# Arduino.net
KiCad netlist of a schematic drawn in Altium Designer
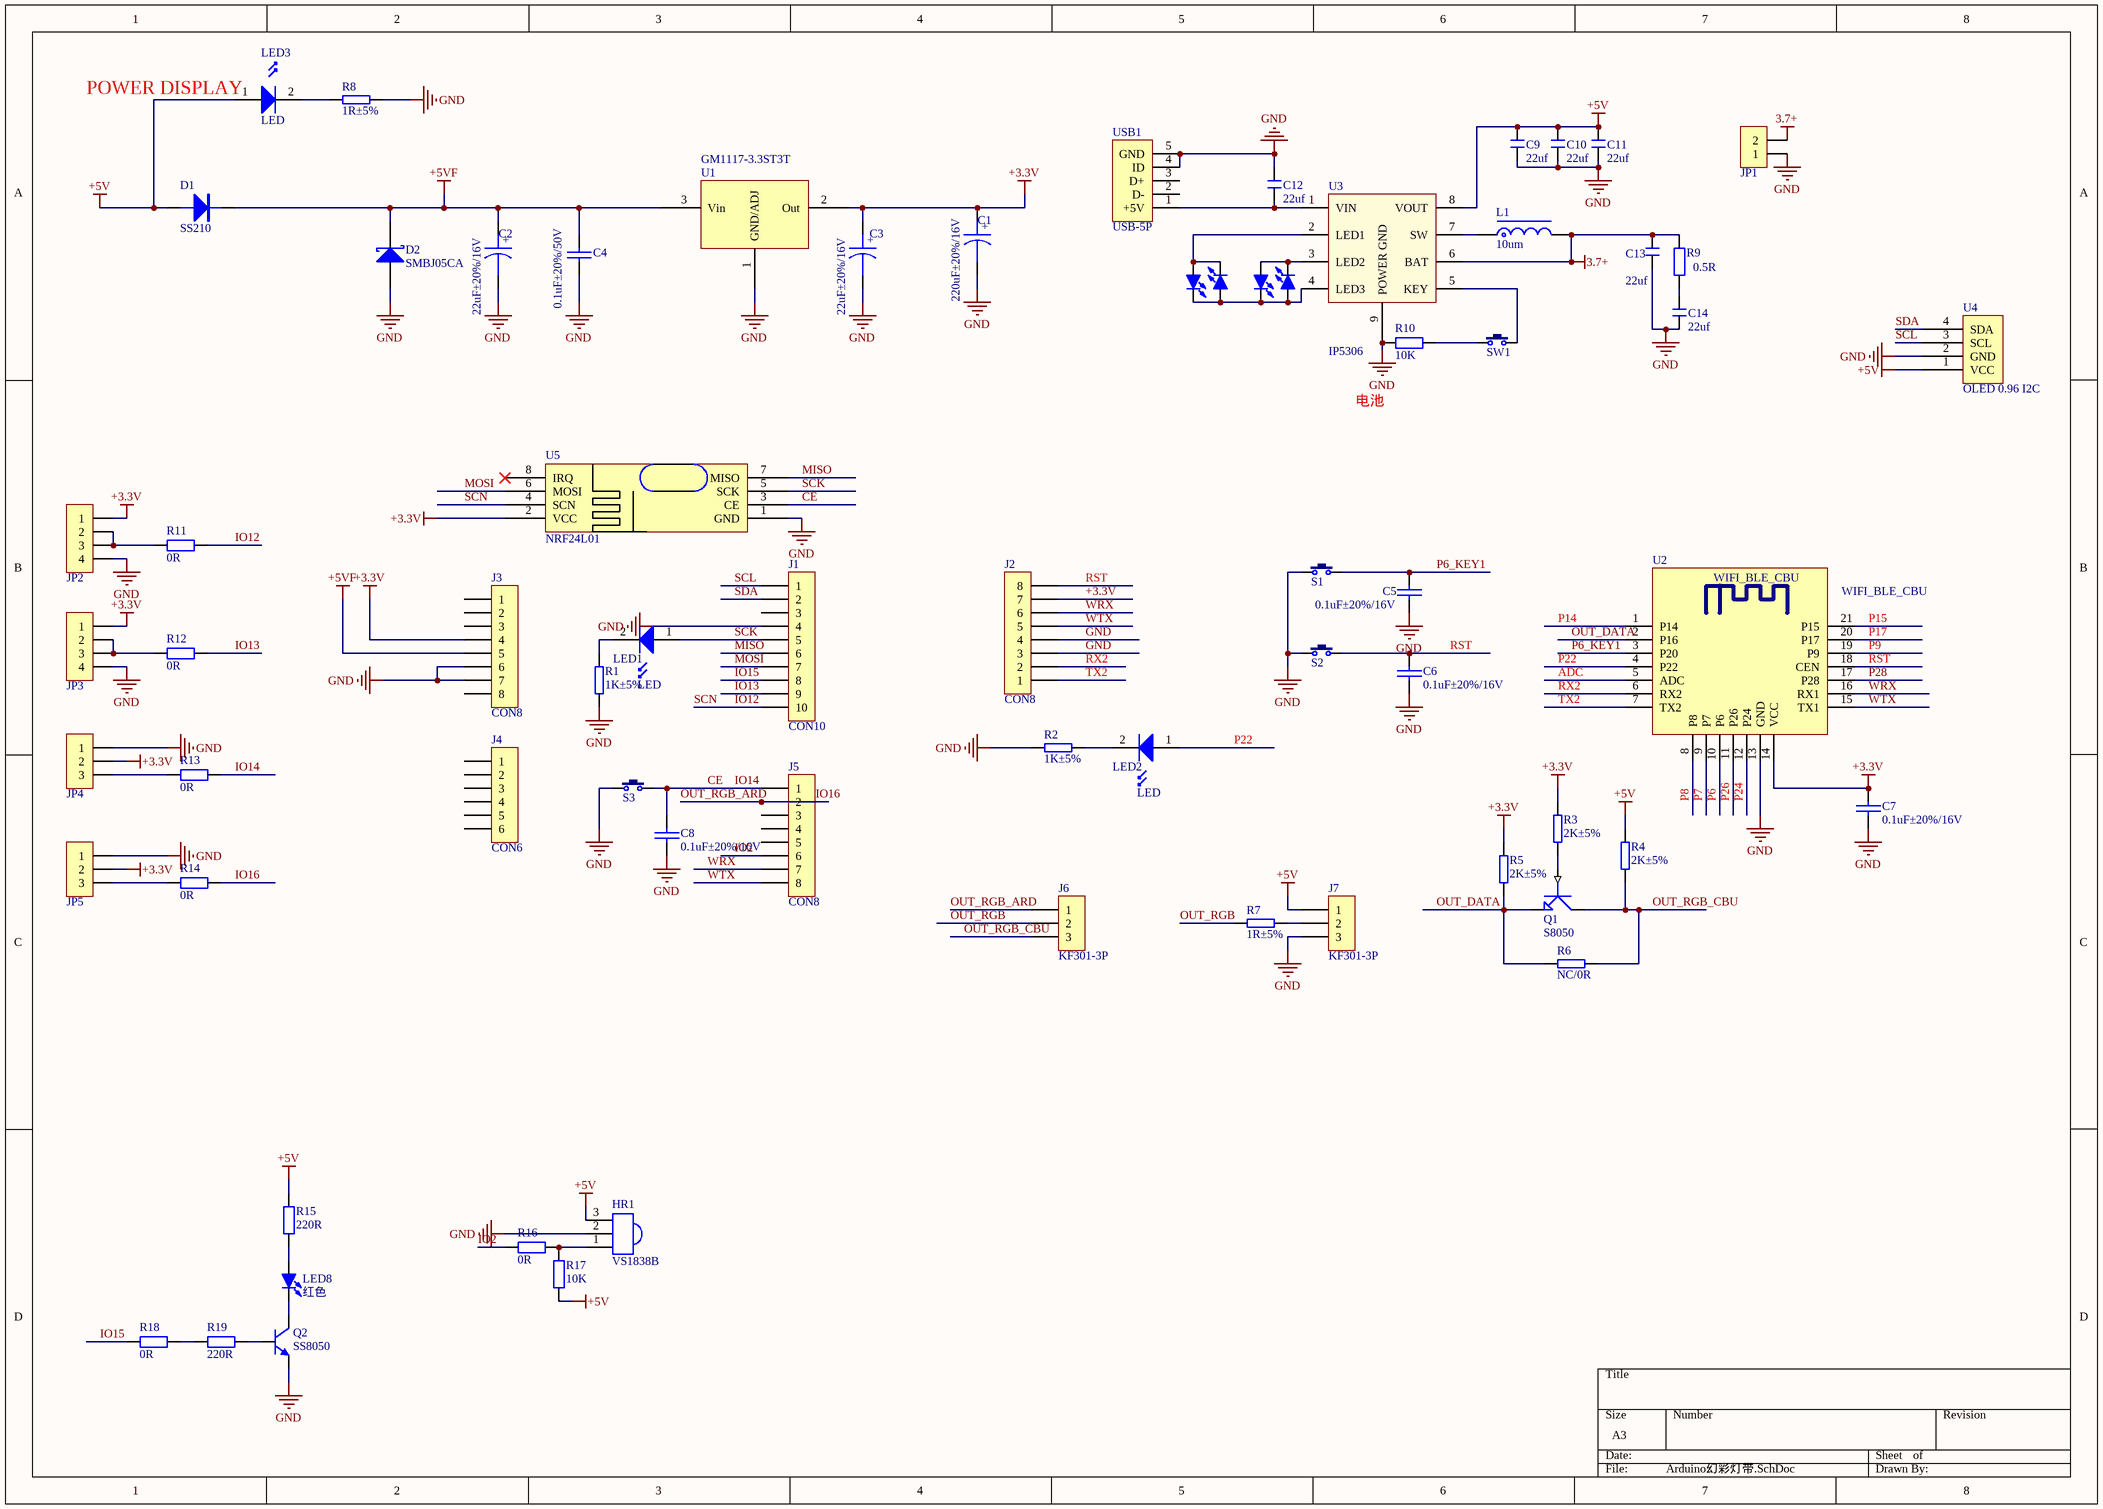
[diagram p0: Arduino幻彩灯带.SchDoc]

(export (version "E")
  (design (tool "Eeschema 10.0.6"))
  (components
    (comp (ref "C1")
      (value "220uF±20%/16V")
      (footprint "CD0.15")
      (description "Capacitor")
      (libsource (lib "*") (part "CAPACITOR POL"))
    )
    (comp (ref "C2")
      (value "22uF±20%/16V")
      (footprint "钽电容B3528")
      (description "Capacitor")
      (libsource (lib "*") (part "CAPACITOR POL"))
    )
    (comp (ref "C3")
      (value "22uF±20%/16V")
      (footprint "钽电容B3528")
      (description "Capacitor")
      (libsource (lib "*") (part "CAPACITOR POL"))
    )
    (comp (ref "C4")
      (value "0.1uF±20%/50V")
      (footprint "C0603")
      (description "Capacitor")
      (libsource (lib "昊华元件库sch") (part "CAP"))
    )
    (comp (ref "C5")
      (value "0.1uF±20%/16V")
      (footprint "C0603")
      (description "Capacitor")
      (libsource (lib "昊华元件库sch") (part "CAP"))
    )
    (comp (ref "C6")
      (value "0.1uF±20%/16V")
      (footprint "C0603")
      (description "Capacitor")
      (libsource (lib "昊华元件库sch") (part "CAP"))
    )
    (comp (ref "C7")
      (value "0.1uF±20%/16V")
      (footprint "C0603")
      (description "Capacitor")
      (libsource (lib "昊华元件库sch") (part "CAP"))
    )
    (comp (ref "C8")
      (value "0.1uF±20%/16V")
      (footprint "C0603")
      (description "Capacitor")
      (libsource (lib "昊华元件库sch") (part "CAP"))
    )
    (comp (ref "C9")
      (value "22uf")
      (footprint "C 0805")
      (description "无极性贴片电容")
      (fields (field (name "版权归属") "源创客"))
      (libsource (lib "电阻-电容-电感") (part "C"))
    )
    (comp (ref "C10")
      (value "22uf")
      (footprint "C 0805")
      (description "无极性贴片电容")
      (fields (field (name "版权归属") "源创客"))
      (libsource (lib "电阻-电容-电感") (part "C"))
    )
    (comp (ref "C11")
      (value "22uf")
      (footprint "C 0805")
      (description "无极性贴片电容")
      (fields (field (name "版权归属") "源创客"))
      (libsource (lib "电阻-电容-电感") (part "C"))
    )
    (comp (ref "C12")
      (value "22uf")
      (footprint "C 0805")
      (description "无极性贴片电容")
      (fields (field (name "版权归属") "源创客"))
      (libsource (lib "电阻-电容-电感") (part "C"))
    )
    (comp (ref "C13")
      (value "22uf")
      (footprint "C 0805")
      (description "无极性贴片电容")
      (fields (field (name "版权归属") "源创客"))
      (libsource (lib "电阻-电容-电感") (part "C"))
    )
    (comp (ref "C14")
      (value "22uf")
      (footprint "C 0805")
      (description "无极性贴片电容")
      (fields (field (name "版权归属") "源创客"))
      (libsource (lib "电阻-电容-电感") (part "C"))
    )
    (comp (ref "D1")
      (value "SS210")
      (footprint "SMA(DO-214AC)")
      (description "Diode")
      (libsource (lib "小马元件库sch") (part "Diode1"))
    )
    (comp (ref "D2")
      (value "SMBJ05CA")
      (footprint "SMB(DO-214AA)")
      (description "Schottky Diode")
      (fields (field (name "MFR") "Toshiba"))
      (libsource (lib "Miscellaneous Devices") (part "D Schottky"))
    )
    (comp (ref "HR1")
      (value "VS1838B")
      (footprint "VS1838B-B")
      (description "红外接收头")
      (fields (field (name "版权归属") "源创客"))
      (libsource (lib "传感元件") (part "VS1838B"))
    )
    (comp (ref "J1")
      (value "CON10")
      (footprint "HDR1X10Z")
      (description "Connector")
      (libsource (lib "小马元件库sch") (part "CON10"))
    )
    (comp (ref "J2")
      (value "CON8")
      (footprint "HDR1X8Z")
      (description "Connector")
      (libsource (lib "小马元件库sch") (part "CON8"))
    )
    (comp (ref "J3")
      (value "CON8")
      (footprint "HDR1X8Z")
      (description "Connector")
      (libsource (lib "") (part "CON8_1"))
    )
    (comp (ref "J4")
      (value "CON6")
      (footprint "HDR1X6Z")
      (description "Connector")
      (libsource (lib "小马元件库sch") (part "CON6"))
    )
    (comp (ref "J5")
      (value "CON8")
      (footprint "HDR1X8Z")
      (description "Connector")
      (libsource (lib "") (part "CON8_1"))
    )
    (comp (ref "J6")
      (value "KF301-3P")
      (footprint "SIP3 - 2.54")
      (description "Connector")
      (libsource (lib "小马元件库sch") (part "CON3"))
    )
    (comp (ref "J7")
      (value "KF301-3P")
      (footprint "SIP3 - 2.54")
      (description "Connector")
      (libsource (lib "小马元件库sch") (part "CON3"))
    )
    (comp (ref "JP1")
      (value "HDR-1X2")
      (footprint "XH2.54-2P_H")
      (description "2P接插件")
      (fields (field (name "版权归属") "源创客"))
      (libsource (lib "接插件") (part "Header 2"))
    )
    (comp (ref "JP2")
      (value "HDR-1X4")
      (footprint "HDR-1X4_M")
      (description "4P接插件")
      (fields (field (name "版权归属") "源创客"))
      (libsource (lib "接插件") (part "Header 4"))
    )
    (comp (ref "JP3")
      (value "HDR-1X4")
      (footprint "HDR-1X4_M")
      (description "4P接插件")
      (fields (field (name "版权归属") "源创客"))
      (libsource (lib "接插件") (part "Header 4"))
    )
    (comp (ref "JP4")
      (value "HDR-1X3")
      (footprint "HDR-1X3_M")
      (description "3P接插件")
      (fields (field (name "版权归属") "源创客"))
      (libsource (lib "接插件") (part "Header 3"))
    )
    (comp (ref "JP5")
      (value "HDR-1X3")
      (footprint "HDR-1X3_M")
      (description "3P接插件")
      (fields (field (name "版权归属") "源创客"))
      (libsource (lib "接插件") (part "Header 3"))
    )
    (comp (ref "L1")
      (value "10um")
      (footprint "CD54")
      (description "贴片功率电感")
      (fields (field (name "版权归属") "源创客"))
      (libsource (lib "电阻-电容-电感") (part "L-CD"))
    )
    (comp (ref "LED1")
      (value "LED")
      (footprint "LED0805_1")
      (fields (field (name "PUBLISHER") "*"))
      (libsource (lib "小马元件库sch") (part "LED"))
    )
    (comp (ref "LED2")
      (value "LED")
      (footprint "LED0805_1")
      (fields (field (name "PUBLISHER") "*"))
      (libsource (lib "小马元件库sch") (part "LED"))
    )
    (comp (ref "LED3")
      (value "LED")
      (footprint "LED0805_1")
      (fields (field (name "PUBLISHER") "*"))
      (libsource (lib "小马元件库sch") (part "LED"))
    )
    (comp (ref "LED4")
      (value "蓝色")
      (footprint "LED 0805B")
      (description "贴片LED")
      (fields (field (name "版权归属") "源创客"))
      (libsource (lib "LED") (part "LED-SMD"))
    )
    (comp (ref "LED5")
      (value "蓝色")
      (footprint "LED 0805B")
      (description "贴片LED")
      (fields (field (name "版权归属") "源创客"))
      (libsource (lib "LED") (part "LED-SMD"))
    )
    (comp (ref "LED6")
      (value "蓝色")
      (footprint "LED 0805B")
      (description "贴片LED")
      (fields (field (name "版权归属") "源创客"))
      (libsource (lib "LED") (part "LED-SMD"))
    )
    (comp (ref "LED7")
      (value "蓝色")
      (footprint "LED 0805B")
      (description "贴片LED")
      (fields (field (name "版权归属") "源创客"))
      (libsource (lib "LED") (part "LED-SMD"))
    )
    (comp (ref "LED8")
      (value "红色")
      (footprint "LED 5MM-B")
      (description "5mm插件LED")
      (fields (field (name "版权归属") "源创客"))
      (libsource (lib "LED") (part "LED-5MM"))
    )
    (comp (ref "Q1")
      (value "S8050")
      (footprint "SOT-23-NPN")
      (description "NPN Transistor")
      (libsource (lib "小马元件库sch") (part "NPN"))
    )
    (comp (ref "Q2")
      (value "SS8050")
      (footprint "SOT23-3N")
      (description "高频放大-NPN型")
      (fields (field (name "版权归属") "源创客"))
      (libsource (lib "三极管") (part "8050-SMD"))
    )
    (comp (ref "R1") (value "1K±5%") (footprint "R0603") (libsource (lib "昊华元件库sch") (part "RES5")))
    (comp (ref "R2") (value "1K±5%") (footprint "R0603") (libsource (lib "昊华元件库sch") (part "RES5")))
    (comp (ref "R3") (value "2K±5%") (footprint "R0603") (libsource (lib "昊华元件库sch") (part "RES5")))
    (comp (ref "R4") (value "2K±5%") (footprint "R0603") (libsource (lib "昊华元件库sch") (part "RES5")))
    (comp (ref "R5") (value "2K±5%") (footprint "R0603") (libsource (lib "昊华元件库sch") (part "RES5")))
    (comp (ref "R6") (value "NC/0R") (footprint "R0603") (libsource (lib "昊华元件库sch") (part "RES5")))
    (comp (ref "R7") (value "1R±5%") (footprint "R0603") (libsource (lib "昊华元件库sch") (part "RES5")))
    (comp (ref "R8") (value "1R±5%") (footprint "R0603") (libsource (lib "昊华元件库sch") (part "RES5")))
    (comp (ref "R9")
      (value "0.5R")
      (footprint "R 0805")
      (description "贴片电阻")
      (fields (field (name "版权归属") "源创客"))
      (libsource (lib "电阻-电容-电感") (part "R"))
    )
    (comp (ref "R10")
      (value "10K")
      (footprint "R 0805")
      (description "贴片电阻")
      (fields (field (name "版权归属") "源创客"))
      (libsource (lib "电阻-电容-电感") (part "R"))
    )
    (comp (ref "R11")
      (value "0R")
      (footprint "R 0603")
      (description "贴片电阻")
      (fields (field (name "版权归属") "源创客"))
      (libsource (lib "电阻-电容-电感") (part "R"))
    )
    (comp (ref "R12")
      (value "0R")
      (footprint "R 0603")
      (description "贴片电阻")
      (fields (field (name "版权归属") "源创客"))
      (libsource (lib "电阻-电容-电感") (part "R"))
    )
    (comp (ref "R13")
      (value "0R")
      (footprint "R 0603")
      (description "贴片电阻")
      (fields (field (name "版权归属") "源创客"))
      (libsource (lib "电阻-电容-电感") (part "R"))
    )
    (comp (ref "R14")
      (value "0R")
      (footprint "R 0603")
      (description "贴片电阻")
      (fields (field (name "版权归属") "源创客"))
      (libsource (lib "电阻-电容-电感") (part "R"))
    )
    (comp (ref "R15")
      (value "220R")
      (footprint "R 0603")
      (description "贴片电阻")
      (fields (field (name "版权归属") "源创客"))
      (libsource (lib "电阻-电容-电感") (part "R"))
    )
    (comp (ref "R16")
      (value "0R")
      (footprint "R 0603")
      (description "贴片电阻")
      (fields (field (name "版权归属") "源创客"))
      (libsource (lib "电阻-电容-电感") (part "R"))
    )
    (comp (ref "R17")
      (value "10K")
      (footprint "R 0603")
      (description "贴片电阻")
      (fields (field (name "版权归属") "源创客"))
      (libsource (lib "电阻-电容-电感") (part "R"))
    )
    (comp (ref "R18")
      (value "0R")
      (footprint "R 0603")
      (description "贴片电阻")
      (fields (field (name "版权归属") "源创客"))
      (libsource (lib "电阻-电容-电感") (part "R"))
    )
    (comp (ref "R19")
      (value "220R")
      (footprint "R 0603")
      (description "贴片电阻")
      (fields (field (name "版权归属") "源创客"))
      (libsource (lib "电阻-电容-电感") (part "R"))
    )
    (comp (ref "S1")
      (value "3x6x5")
      (footprint "TSW SMD-3*6*2.5")
      (description "3x6轻触开关")
      (fields (field (name "版权归属") "源创客"))
      (libsource (lib "按键-开关") (part "TSW 3x6"))
    )
    (comp (ref "S2")
      (value "3x6x5")
      (footprint "TSW SMD-3*6*2.5")
      (description "3x6轻触开关")
      (fields (field (name "版权归属") "源创客"))
      (libsource (lib "按键-开关") (part "TSW 3x6"))
    )
    (comp (ref "S3")
      (value "3x6x5")
      (footprint "TSW SMD-3*6*2.5")
      (description "3x6轻触开关")
      (fields (field (name "版权归属") "源创客"))
      (libsource (lib "按键-开关") (part "TSW 3x6"))
    )
    (comp (ref "SW1")
      (value "3x6x5")
      (footprint "TSW SMD-3*6*2.5")
      (description "3x6轻触开关")
      (fields (field (name "版权归属") "源创客"))
      (libsource (lib "按键-开关") (part "TSW 3x6"))
    )
    (comp (ref "U1") (value "GM1117-3.3ST3T") (footprint "SOT-223") (libsource (lib "mylib") (part "GM1117")))
    (comp (ref "U2")
      (value "WIFI_BLE_CBU")
      (footprint "WIFI_BLE_CBU")
      (description "Module")
      (libsource (lib "TYModeSchlib V03") (part "WIFI_BLE_CBU"))
    )
    (comp (ref "U3")
      (value "IP5306")
      (footprint "5306")
      (description "锂电池充放电管理芯片")
      (libsource (lib "电源管理类芯片") (part "IP5306"))
    )
    (comp (ref "U4")
      (value "OLED 0.96 I2C")
      (footprint "OLED 0.96 I2C")
      (libsource (lib "显示器件") (part "OLED 0.96 I2C"))
    )
    (comp (ref "U5")
      (value "NRF24L01")
      (footprint "NRF24L01")
      (description "2.4G无线模块")
      (libsource (lib "模块") (part "NRF24L01"))
    )
    (comp (ref "USB1")
      (value "USB-5P")
      (footprint "USB-MICRO_B")
      (description "微型USB母座")
      (fields (field (name "版权归属") "源创客"))
      (libsource (lib "接口类") (part "USB-5P"))
    )
  )
  (nets
    (net (code "1") (name "+3.3V") (class "Default")
      (node (ref "C1") (pin "1") (pinfunction "1_1") (pintype "passive"))
      (node (ref "C3") (pin "1") (pinfunction "1_1") (pintype "passive"))
      (node (ref "C7") (pin "2") (pinfunction "2_2") (pintype "passive"))
      (node (ref "J2") (pin "7") (pinfunction "7_7") (pintype "passive"))
      (node (ref "J3") (pin "4") (pinfunction "4_4") (pintype "passive"))
      (node (ref "JP2") (pin "1") (pinfunction "1_1") (pintype "passive"))
      (node (ref "JP3") (pin "1") (pinfunction "1_1") (pintype "passive"))
      (node (ref "JP4") (pin "2") (pinfunction "2_2") (pintype "passive"))
      (node (ref "JP5") (pin "2") (pinfunction "2_2") (pintype "passive"))
      (node (ref "R3") (pin "1") (pinfunction "1_1") (pintype "passive"))
      (node (ref "R5") (pin "1") (pinfunction "1_1") (pintype "passive"))
      (node (ref "U1") (pin "2") (pinfunction "Out_2") (pintype "passive"))
      (node (ref "U2") (pin "14") (pinfunction "VCC_14") (pintype "passive"))
      (node (ref "U5") (pin "2") (pinfunction "VCC_2") (pintype "power_in"))
    )
    (net (code "2") (name "+5V") (class "Default")
      (node (ref "C10") (pin "2") (pinfunction "2_2") (pintype "passive"))
      (node (ref "C11") (pin "2") (pinfunction "2_2") (pintype "passive"))
      (node (ref "C9") (pin "2") (pinfunction "2_2") (pintype "passive"))
      (node (ref "D1") (pin "1") (pinfunction "1_1") (pintype "passive"))
      (node (ref "HR1") (pin "3") (pinfunction "E_3") (pintype "passive"))
      (node (ref "J7") (pin "1") (pinfunction "1_1") (pintype "passive"))
      (node (ref "LED3") (pin "1") (pinfunction "1_1") (pintype "passive"))
      (node (ref "R15") (pin "2") (pinfunction "2_2") (pintype "passive"))
      (node (ref "R17") (pin "1") (pinfunction "1_1") (pintype "passive"))
      (node (ref "R4") (pin "1") (pinfunction "1_1") (pintype "passive"))
      (node (ref "U3") (pin "8") (pinfunction "VOUT_8") (pintype "passive"))
      (node (ref "U4") (pin "1") (pinfunction "VCC_1") (pintype "power_in"))
    )
    (net (code "3") (name "+5VF") (class "Default")
      (node (ref "C2") (pin "1") (pinfunction "1_1") (pintype "passive"))
      (node (ref "C4") (pin "1") (pinfunction "1_1") (pintype "passive"))
      (node (ref "D1") (pin "2") (pinfunction "2_2") (pintype "passive"))
      (node (ref "D2") (pin "2") (pinfunction "K_2") (pintype "passive"))
      (node (ref "J3") (pin "5") (pinfunction "5_5") (pintype "passive"))
      (node (ref "U1") (pin "3") (pinfunction "Vin_3") (pintype "passive"))
    )
    (net (code "4") (name "/ADC") (class "Default")
      (node (ref "U2") (pin "5") (pinfunction "ADC_5") (pintype "passive"))
    )
    (net (code "5") (name "/CE") (class "Default")
      (node (ref "C8") (pin "2") (pinfunction "2_2") (pintype "passive"))
      (node (ref "J5") (pin "1") (pinfunction "1_1") (pintype "passive"))
      (node (ref "R13") (pin "2") (pinfunction "2_2") (pintype "passive"))
      (node (ref "S3") (pin "2") (pinfunction "2_2") (pintype "passive"))
      (node (ref "U5") (pin "3") (pinfunction "CE_3") (pintype "power_in"))
    )
    (net (code "6") (name "/IO2") (class "Default")
      (node (ref "J5") (pin "6") (pinfunction "6_6") (pintype "passive"))
      (node (ref "R16") (pin "1") (pinfunction "1_1") (pintype "passive"))
    )
    (net (code "7") (name "/IO12") (class "Default")
      (node (ref "J1") (pin "10") (pinfunction "10_10") (pintype "passive"))
      (node (ref "R11") (pin "2") (pinfunction "2_2") (pintype "passive"))
      (node (ref "U5") (pin "4") (pinfunction "SCN_4") (pintype "power_in"))
    )
    (net (code "8") (name "/IO13") (class "Default")
      (node (ref "J1") (pin "9") (pinfunction "9_9") (pintype "passive"))
      (node (ref "R12") (pin "2") (pinfunction "2_2") (pintype "passive"))
    )
    (net (code "9") (name "/IO15") (class "Default")
      (node (ref "J1") (pin "8") (pinfunction "8_8") (pintype "passive"))
      (node (ref "R18") (pin "1") (pinfunction "1_1") (pintype "passive"))
    )
    (net (code "10") (name "/IO16") (class "Default")
      (node (ref "J5") (pin "2") (pinfunction "2_2") (pintype "passive"))
      (node (ref "J6") (pin "1") (pinfunction "1_1") (pintype "passive"))
      (node (ref "R14") (pin "2") (pinfunction "2_2") (pintype "passive"))
    )
    (net (code "11") (name "/MISO") (class "Default")
      (node (ref "J1") (pin "6") (pinfunction "6_6") (pintype "passive"))
      (node (ref "U5") (pin "7") (pinfunction "MISO_7") (pintype "power_in"))
    )
    (net (code "12") (name "/MOSI") (class "Default")
      (node (ref "J1") (pin "7") (pinfunction "7_7") (pintype "passive"))
      (node (ref "U5") (pin "6") (pinfunction "MOSI_6") (pintype "power_in"))
    )
    (net (code "13") (name "/OUT_DATA") (class "Default")
      (node (ref "Q1") (pin "1") (pinfunction "E_1") (pintype "passive"))
      (node (ref "R5") (pin "2") (pinfunction "2_2") (pintype "passive"))
      (node (ref "R6") (pin "1") (pinfunction "1_1") (pintype "passive"))
      (node (ref "U2") (pin "2") (pinfunction "P16_2") (pintype "passive"))
    )
    (net (code "14") (name "/OUT_RGB") (class "Default")
      (node (ref "J6") (pin "2") (pinfunction "2_2") (pintype "passive"))
      (node (ref "R7") (pin "1") (pinfunction "1_1") (pintype "passive"))
    )
    (net (code "15") (name "/OUT_RGB_CBU") (class "Default")
      (node (ref "J6") (pin "3") (pinfunction "3_3") (pintype "passive"))
      (node (ref "Q1") (pin "3") (pinfunction "C_3") (pintype "passive"))
      (node (ref "R4") (pin "2") (pinfunction "2_2") (pintype "passive"))
      (node (ref "R6") (pin "2") (pinfunction "2_2") (pintype "passive"))
    )
    (net (code "16") (name "/P6") (class "Default")
      (node (ref "U2") (pin "10") (pinfunction "P6_10") (pintype "passive"))
    )
    (net (code "17") (name "/P6_KEY1") (class "Default")
      (node (ref "C5") (pin "2") (pinfunction "2_2") (pintype "passive"))
      (node (ref "S1") (pin "2") (pinfunction "2_2") (pintype "passive"))
      (node (ref "U2") (pin "3") (pinfunction "P20_3") (pintype "passive"))
    )
    (net (code "18") (name "/P7") (class "Default")
      (node (ref "U2") (pin "9") (pinfunction "P7_9") (pintype "passive"))
    )
    (net (code "19") (name "/P8") (class "Default")
      (node (ref "U2") (pin "8") (pinfunction "P8_8") (pintype "passive"))
    )
    (net (code "20") (name "/P9") (class "Default")
      (node (ref "U2") (pin "19") (pinfunction "P9_19") (pintype "passive"))
    )
    (net (code "21") (name "/P14") (class "Default")
      (node (ref "U2") (pin "1") (pinfunction "P14_1") (pintype "passive"))
    )
    (net (code "22") (name "/P15") (class "Default")
      (node (ref "U2") (pin "21") (pinfunction "P15_21") (pintype "passive"))
    )
    (net (code "23") (name "/P17") (class "Default")
      (node (ref "U2") (pin "20") (pinfunction "P17_20") (pintype "passive"))
    )
    (net (code "24") (name "/P22") (class "Default")
      (node (ref "LED2") (pin "1") (pinfunction "1_1") (pintype "passive"))
      (node (ref "U2") (pin "4") (pinfunction "P22_4") (pintype "passive"))
    )
    (net (code "25") (name "/P24") (class "Default")
      (node (ref "U2") (pin "12") (pinfunction "P24_12") (pintype "passive"))
    )
    (net (code "26") (name "/P26") (class "Default")
      (node (ref "U2") (pin "11") (pinfunction "P26_11") (pintype "passive"))
    )
    (net (code "27") (name "/P28") (class "Default")
      (node (ref "U2") (pin "17") (pinfunction "P28_17") (pintype "passive"))
    )
    (net (code "28") (name "/RST") (class "Default")
      (node (ref "C6") (pin "1") (pinfunction "1_1") (pintype "passive"))
      (node (ref "J2") (pin "8") (pinfunction "8_8") (pintype "passive"))
      (node (ref "S2") (pin "2") (pinfunction "2_2") (pintype "passive"))
      (node (ref "U2") (pin "18") (pinfunction "CEN_18") (pintype "passive"))
    )
    (net (code "29") (name "/RX2") (class "Default")
      (node (ref "J2") (pin "2") (pinfunction "2_2") (pintype "passive"))
      (node (ref "U2") (pin "6") (pinfunction "RX2_6") (pintype "passive"))
    )
    (net (code "30") (name "/SCK") (class "Default")
      (node (ref "J1") (pin "5") (pinfunction "5_5") (pintype "passive"))
      (node (ref "LED1") (pin "1") (pinfunction "1_1") (pintype "passive"))
      (node (ref "U5") (pin "5") (pinfunction "SCK_5") (pintype "power_in"))
    )
    (net (code "31") (name "/SCL") (class "Default")
      (node (ref "J1") (pin "1") (pinfunction "1_1") (pintype "passive"))
      (node (ref "U4") (pin "3") (pinfunction "SCL_3") (pintype "power_in"))
    )
    (net (code "32") (name "/SDA") (class "Default")
      (node (ref "J1") (pin "2") (pinfunction "2_2") (pintype "passive"))
      (node (ref "U4") (pin "4") (pinfunction "SDA_4") (pintype "power_in"))
    )
    (net (code "33") (name "/TX2") (class "Default")
      (node (ref "J2") (pin "1") (pinfunction "1_1") (pintype "passive"))
      (node (ref "U2") (pin "7") (pinfunction "TX2_7") (pintype "passive"))
    )
    (net (code "34") (name "/WRX") (class "Default")
      (node (ref "J2") (pin "6") (pinfunction "6_6") (pintype "passive"))
      (node (ref "J5") (pin "7") (pinfunction "7_7") (pintype "passive"))
      (node (ref "U2") (pin "16") (pinfunction "RX1_16") (pintype "passive"))
    )
    (net (code "35") (name "/WTX") (class "Default")
      (node (ref "J2") (pin "5") (pinfunction "5_5") (pintype "passive"))
      (node (ref "J5") (pin "8") (pinfunction "8_8") (pintype "passive"))
      (node (ref "U2") (pin "15") (pinfunction "TX1_15") (pintype "passive"))
    )
    (net (code "36") (name "3.7+") (class "Default")
      (node (ref "C13") (pin "2") (pinfunction "2_2") (pintype "passive"))
      (node (ref "JP1") (pin "2") (pinfunction "2_2") (pintype "passive"))
      (node (ref "L1") (pin "2") (pinfunction "2_2") (pintype "passive"))
      (node (ref "R9") (pin "2") (pinfunction "2_2") (pintype "passive"))
      (node (ref "U3") (pin "6") (pinfunction "BAT_6") (pintype "passive"))
    )
    (net (code "37") (name "GND") (class "Default")
      (node (ref "C1") (pin "2") (pinfunction "2_2") (pintype "passive"))
      (node (ref "C10") (pin "1") (pinfunction "1_1") (pintype "passive"))
      (node (ref "C11") (pin "1") (pinfunction "1_1") (pintype "passive"))
      (node (ref "C12") (pin "2") (pinfunction "2_2") (pintype "passive"))
      (node (ref "C13") (pin "1") (pinfunction "1_1") (pintype "passive"))
      (node (ref "C14") (pin "1") (pinfunction "1_1") (pintype "passive"))
      (node (ref "C2") (pin "2") (pinfunction "2_2") (pintype "passive"))
      (node (ref "C3") (pin "2") (pinfunction "2_2") (pintype "passive"))
      (node (ref "C4") (pin "2") (pinfunction "2_2") (pintype "passive"))
      (node (ref "C5") (pin "1") (pinfunction "1_1") (pintype "passive"))
      (node (ref "C6") (pin "2") (pinfunction "2_2") (pintype "passive"))
      (node (ref "C7") (pin "1") (pinfunction "1_1") (pintype "passive"))
      (node (ref "C8") (pin "1") (pinfunction "1_1") (pintype "passive"))
      (node (ref "C9") (pin "1") (pinfunction "1_1") (pintype "passive"))
      (node (ref "D2") (pin "1") (pinfunction "A_1") (pintype "passive"))
      (node (ref "HR1") (pin "2") (pinfunction "K_2") (pintype "passive"))
      (node (ref "J1") (pin "4") (pinfunction "4_4") (pintype "passive"))
      (node (ref "J2") (pin "3") (pinfunction "3_3") (pintype "passive"))
      (node (ref "J2") (pin "4") (pinfunction "4_4") (pintype "passive"))
      (node (ref "J3") (pin "6") (pinfunction "6_6") (pintype "passive"))
      (node (ref "J3") (pin "7") (pinfunction "7_7") (pintype "passive"))
      (node (ref "J7") (pin "3") (pinfunction "3_3") (pintype "passive"))
      (node (ref "JP1") (pin "1") (pinfunction "1_1") (pintype "passive"))
      (node (ref "JP2") (pin "4") (pinfunction "4_4") (pintype "passive"))
      (node (ref "JP3") (pin "4") (pinfunction "4_4") (pintype "passive"))
      (node (ref "JP4") (pin "1") (pinfunction "1_1") (pintype "passive"))
      (node (ref "JP5") (pin "1") (pinfunction "1_1") (pintype "passive"))
      (node (ref "Q2") (pin "2") (pinfunction "E_2") (pintype "passive"))
      (node (ref "R1") (pin "1") (pinfunction "1_1") (pintype "passive"))
      (node (ref "R10") (pin "1") (pinfunction "1_1") (pintype "passive"))
      (node (ref "R2") (pin "2") (pinfunction "2_2") (pintype "passive"))
      (node (ref "R8") (pin "2") (pinfunction "2_2") (pintype "passive"))
      (node (ref "S1") (pin "1") (pinfunction "1_1") (pintype "passive"))
      (node (ref "S2") (pin "1") (pinfunction "1_1") (pintype "passive"))
      (node (ref "S3") (pin "1") (pinfunction "1_1") (pintype "passive"))
      (node (ref "U1") (pin "1") (pinfunction "GND/ADJ_1") (pintype "passive"))
      (node (ref "U2") (pin "13") (pinfunction "GND_13") (pintype "passive"))
      (node (ref "U3") (pin "9") (pinfunction "POWER_GND_9") (pintype "power_in"))
      (node (ref "U4") (pin "2") (pinfunction "GND_2") (pintype "power_in"))
      (node (ref "U5") (pin "1") (pinfunction "GND_1") (pintype "power_in"))
      (node (ref "USB1") (pin "4") (pinfunction "ID_4") (pintype "passive"))
      (node (ref "USB1") (pin "5") (pinfunction "GND_5") (pintype "passive"))
    )
    (net (code "38") (name "Net-(C14-Pad2)") (class "Default")
      (node (ref "C14") (pin "2") (pinfunction "2_2") (pintype "passive"))
      (node (ref "R9") (pin "1") (pinfunction "1_1") (pintype "passive"))
    )
    (net (code "39") (name "Net-(HR1-A)") (class "Default")
      (node (ref "HR1") (pin "1") (pinfunction "A_1") (pintype "passive"))
      (node (ref "R16") (pin "2") (pinfunction "2_2") (pintype "passive"))
      (node (ref "R17") (pin "2") (pinfunction "2_2") (pintype "passive"))
    )
    (net (code "40") (name "Net-(J7-Pad2)") (class "Default")
      (node (ref "J7") (pin "2") (pinfunction "2_2") (pintype "passive"))
      (node (ref "R7") (pin "2") (pinfunction "2_2") (pintype "passive"))
    )
    (net (code "41") (name "Net-(JP2-Pad2)") (class "Default")
      (node (ref "JP2") (pin "2") (pinfunction "2_2") (pintype "passive"))
      (node (ref "JP2") (pin "3") (pinfunction "3_3") (pintype "passive"))
      (node (ref "R11") (pin "1") (pinfunction "1_1") (pintype "passive"))
    )
    (net (code "42") (name "Net-(JP3-Pad2)") (class "Default")
      (node (ref "JP3") (pin "2") (pinfunction "2_2") (pintype "passive"))
      (node (ref "JP3") (pin "3") (pinfunction "3_3") (pintype "passive"))
      (node (ref "R12") (pin "1") (pinfunction "1_1") (pintype "passive"))
    )
    (net (code "43") (name "Net-(JP4-Pad3)") (class "Default")
      (node (ref "JP4") (pin "3") (pinfunction "3_3") (pintype "passive"))
      (node (ref "R13") (pin "1") (pinfunction "1_1") (pintype "passive"))
    )
    (net (code "44") (name "Net-(JP5-Pad3)") (class "Default")
      (node (ref "JP5") (pin "3") (pinfunction "3_3") (pintype "passive"))
      (node (ref "R14") (pin "1") (pinfunction "1_1") (pintype "passive"))
    )
    (net (code "45") (name "Net-(LED1-Pad2)") (class "Default")
      (node (ref "LED1") (pin "2") (pinfunction "2_2") (pintype "passive"))
      (node (ref "R1") (pin "2") (pinfunction "2_2") (pintype "passive"))
    )
    (net (code "46") (name "Net-(LED2-Pad2)") (class "Default")
      (node (ref "LED2") (pin "2") (pinfunction "2_2") (pintype "passive"))
      (node (ref "R2") (pin "1") (pinfunction "1_1") (pintype "passive"))
    )
    (net (code "47") (name "Net-(LED3-Pad2)") (class "Default")
      (node (ref "LED3") (pin "2") (pinfunction "2_2") (pintype "passive"))
      (node (ref "R8") (pin "1") (pinfunction "1_1") (pintype "passive"))
    )
    (net (code "48") (name "Net-(LED4-A)") (class "Default")
      (node (ref "LED4") (pin "1") (pinfunction "A_1") (pintype "passive"))
      (node (ref "LED5") (pin "1") (pinfunction "A_1") (pintype "passive"))
      (node (ref "LED6") (pin "2") (pinfunction "K_2") (pintype "passive"))
      (node (ref "LED7") (pin "2") (pinfunction "K_2") (pintype "passive"))
      (node (ref "U3") (pin "4") (pinfunction "LED3_4") (pintype "passive"))
    )
    (net (code "49") (name "Net-(LED4-K)") (class "Default")
      (node (ref "LED4") (pin "2") (pinfunction "K_2") (pintype "passive"))
      (node (ref "LED6") (pin "1") (pinfunction "A_1") (pintype "passive"))
      (node (ref "U3") (pin "2") (pinfunction "LED1_2") (pintype "passive"))
    )
    (net (code "50") (name "Net-(LED5-K)") (class "Default")
      (node (ref "LED5") (pin "2") (pinfunction "K_2") (pintype "passive"))
      (node (ref "LED7") (pin "1") (pinfunction "A_1") (pintype "passive"))
      (node (ref "U3") (pin "3") (pinfunction "LED2_3") (pintype "passive"))
    )
    (net (code "51") (name "Net-(LED8-A)") (class "Default")
      (node (ref "LED8") (pin "1") (pinfunction "A_1") (pintype "passive"))
      (node (ref "R15") (pin "1") (pinfunction "1_1") (pintype "passive"))
    )
    (net (code "52") (name "Net-(LED8-K)") (class "Default")
      (node (ref "LED8") (pin "2") (pinfunction "K_2") (pintype "passive"))
      (node (ref "Q2") (pin "3") (pinfunction "C_3") (pintype "passive"))
    )
    (net (code "53") (name "Net-(Q1-B)") (class "Default")
      (node (ref "Q1") (pin "2") (pinfunction "B_2") (pintype "input"))
      (node (ref "R3") (pin "2") (pinfunction "2_2") (pintype "passive"))
    )
    (net (code "54") (name "Net-(Q2-B)") (class "Default")
      (node (ref "Q2") (pin "1") (pinfunction "B_1") (pintype "passive"))
      (node (ref "R19") (pin "2") (pinfunction "2_2") (pintype "passive"))
    )
    (net (code "55") (name "Net-(R10-Pad2)") (class "Default")
      (node (ref "R10") (pin "2") (pinfunction "2_2") (pintype "passive"))
      (node (ref "SW1") (pin "1") (pinfunction "1_1") (pintype "passive"))
    )
    (net (code "56") (name "Net-(R18-Pad2)") (class "Default")
      (node (ref "R18") (pin "2") (pinfunction "2_2") (pintype "passive"))
      (node (ref "R19") (pin "1") (pinfunction "1_1") (pintype "passive"))
    )
    (net (code "57") (name "Net-(U3-KEY)") (class "Default")
      (node (ref "SW1") (pin "2") (pinfunction "2_2") (pintype "passive"))
      (node (ref "U3") (pin "5") (pinfunction "KEY_5") (pintype "passive"))
    )
    (net (code "58") (name "Net-(U3-SW)") (class "Default")
      (node (ref "L1") (pin "1") (pinfunction "1_1") (pintype "passive"))
      (node (ref "U3") (pin "7") (pinfunction "SW_7") (pintype "passive"))
    )
    (net (code "59") (name "Net-(U3-VIN)") (class "Default")
      (node (ref "C12") (pin "1") (pinfunction "1_1") (pintype "passive"))
      (node (ref "U3") (pin "1") (pinfunction "VIN_1") (pintype "passive"))
      (node (ref "USB1") (pin "1") (pinfunction "+5V_1") (pintype "passive"))
    )
    (net (code "60") (name "unconnected-(J1-Pad3)") (class "Default")
      (node (ref "J1") (pin "3") (pinfunction "3_3") (pintype "passive"))
    )
    (net (code "61") (name "unconnected-(J3-Pad1)") (class "Default")
      (node (ref "J3") (pin "1") (pinfunction "1_1") (pintype "passive"))
    )
    (net (code "62") (name "unconnected-(J3-Pad2)") (class "Default")
      (node (ref "J3") (pin "2") (pinfunction "2_2") (pintype "passive"))
    )
    (net (code "63") (name "unconnected-(J3-Pad3)") (class "Default")
      (node (ref "J3") (pin "3") (pinfunction "3_3") (pintype "passive"))
    )
    (net (code "64") (name "unconnected-(J3-Pad8)") (class "Default")
      (node (ref "J3") (pin "8") (pinfunction "8_8") (pintype "passive"))
    )
    (net (code "65") (name "unconnected-(J4-Pad1)") (class "Default")
      (node (ref "J4") (pin "1") (pinfunction "1_1") (pintype "passive"))
    )
    (net (code "66") (name "unconnected-(J4-Pad2)") (class "Default")
      (node (ref "J4") (pin "2") (pinfunction "2_2") (pintype "passive"))
    )
    (net (code "67") (name "unconnected-(J4-Pad3)") (class "Default")
      (node (ref "J4") (pin "3") (pinfunction "3_3") (pintype "passive"))
    )
    (net (code "68") (name "unconnected-(J4-Pad4)") (class "Default")
      (node (ref "J4") (pin "4") (pinfunction "4_4") (pintype "passive"))
    )
    (net (code "69") (name "unconnected-(J4-Pad5)") (class "Default")
      (node (ref "J4") (pin "5") (pinfunction "5_5") (pintype "passive"))
    )
    (net (code "70") (name "unconnected-(J4-Pad6)") (class "Default")
      (node (ref "J4") (pin "6") (pinfunction "6_6") (pintype "passive"))
    )
    (net (code "71") (name "unconnected-(J5-Pad3)") (class "Default")
      (node (ref "J5") (pin "3") (pinfunction "3_3") (pintype "passive"))
    )
    (net (code "72") (name "unconnected-(J5-Pad4)") (class "Default")
      (node (ref "J5") (pin "4") (pinfunction "4_4") (pintype "passive"))
    )
    (net (code "73") (name "unconnected-(J5-Pad5)") (class "Default")
      (node (ref "J5") (pin "5") (pinfunction "5_5") (pintype "passive"))
    )
    (net (code "74") (name "unconnected-(U5-IRQ-Pad8)") (class "Default")
      (node (ref "U5") (pin "8") (pinfunction "IRQ_8") (pintype "power_in+no_connect"))
    )
    (net (code "75") (name "unconnected-(USB1-D+-Pad3)") (class "Default")
      (node (ref "USB1") (pin "3") (pinfunction "D+_3") (pintype "passive"))
    )
    (net (code "76") (name "unconnected-(USB1-D--Pad2)") (class "Default")
      (node (ref "USB1") (pin "2") (pinfunction "D-_2") (pintype "passive"))
    )
  )
)
